# iot_ambilamp_rpi_shield.net
KiCad netlist of a schematic drawn in EAGLE
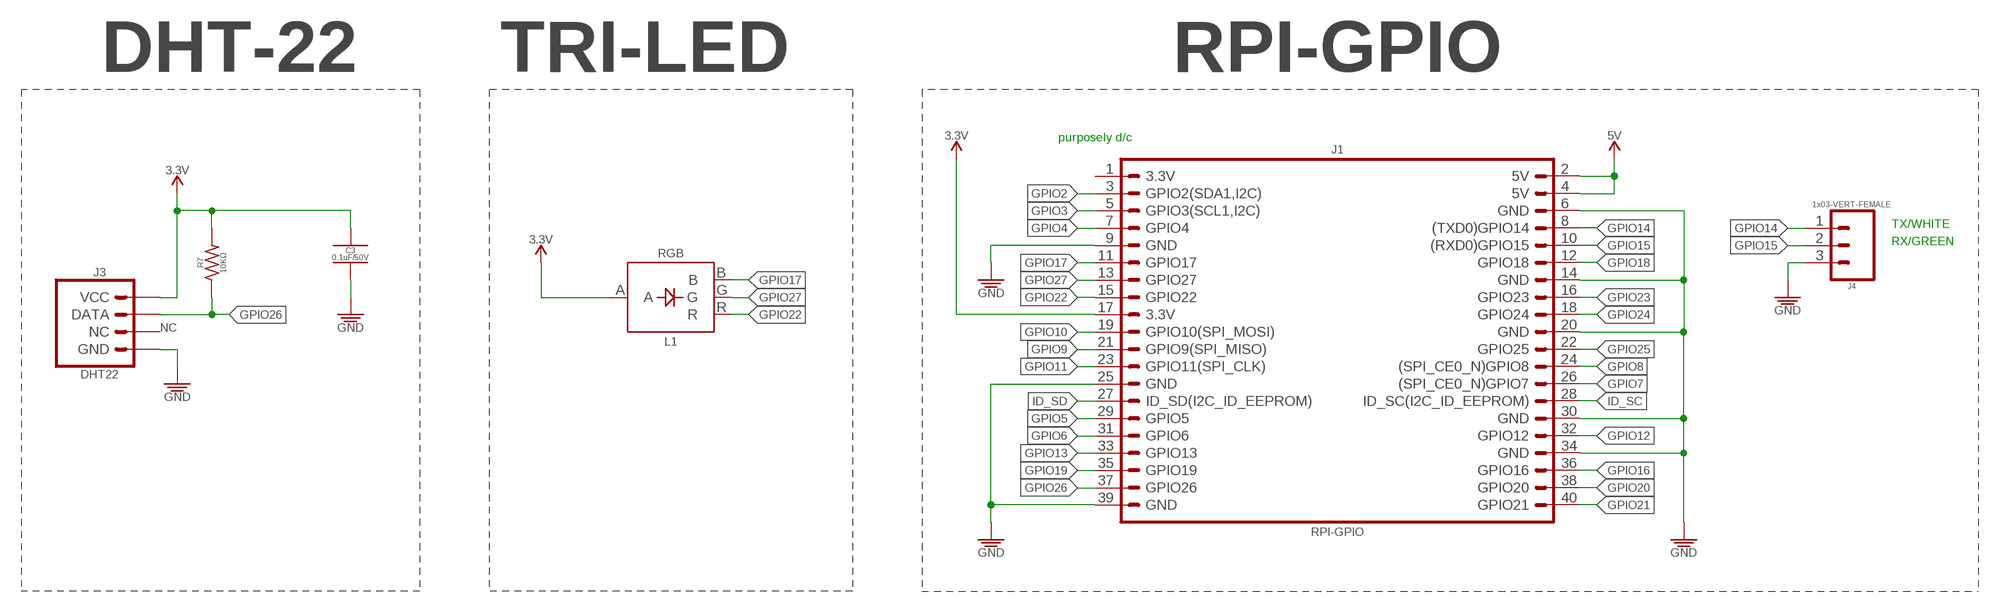
[diagram p0: schematic, sheet 1, part 1 of 2]
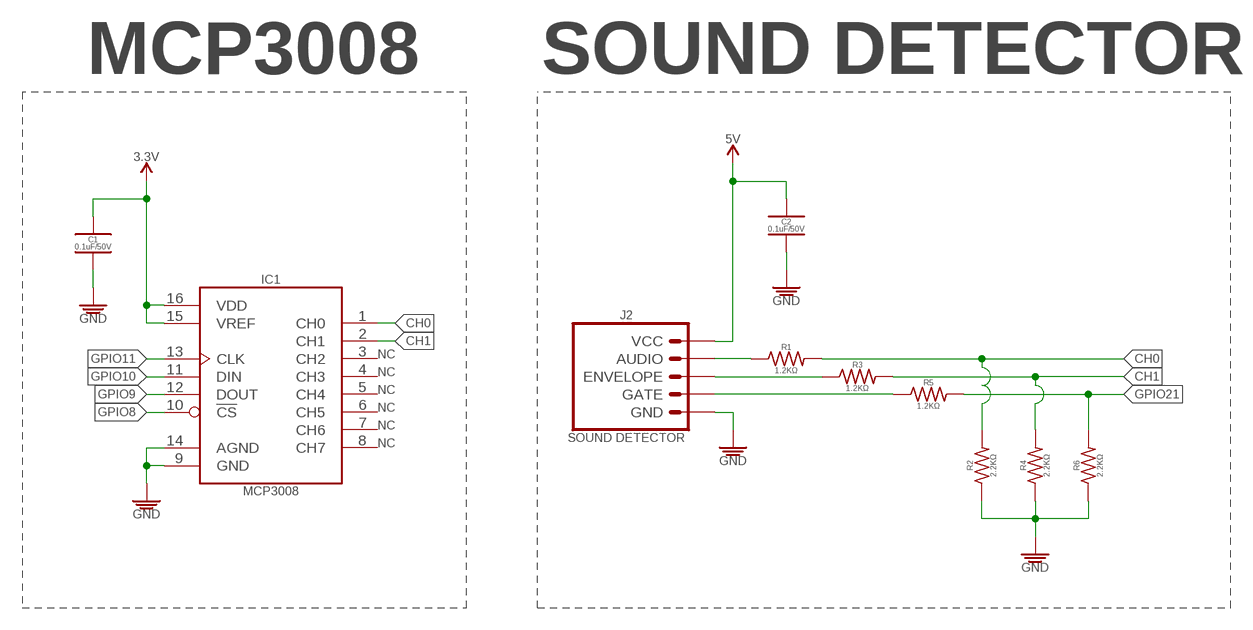
[diagram p1: schematic, sheet 1, part 2 of 2]

(export (version "E")
  (design (tool "Eeschema 10.0.6"))
  (components
    (comp (ref "C1")
      (value "0.1uF/50V")
      (footprint "eagle-import:_CER_SMD-805")
      (fields
        (field (name "MFR") "Murata Electronics North America")
        (field (name "MPN") "GRM21BR71H104KA01L")
        (field (name "CREATOR") "MrSwirlyEyes")
      )
      (libsource (lib "eagle-import") (part "0.1UF_SMD-805_50V-10%"))
    )
    (comp (ref "C2")
      (value "0.1uF/50V")
      (footprint "eagle-import:_CER_SMD-805")
      (fields
        (field (name "MFR") "Murata Electronics North America")
        (field (name "MPN") "GRM21BR71H104KA01L")
        (field (name "CREATOR") "MrSwirlyEyes")
      )
      (libsource (lib "eagle-import") (part "0.1UF_SMD-805_50V-10%"))
    )
    (comp (ref "C3")
      (value "0.1uF/50V")
      (footprint "eagle-import:_CER_SMD-805")
      (fields
        (field (name "MFR") "Murata Electronics North America")
        (field (name "MPN") "GRM21BR71H104KA01L")
        (field (name "CREATOR") "MrSwirlyEyes")
      )
      (libsource (lib "eagle-import") (part "0.1UF_SMD-805_50V-10%"))
    )
    (comp (ref "IC1")
      (value "MCP3008")
      (footprint "eagle-import:SO-16")
      (fields
        (field (name "MFR") "Microchip Technology")
        (field (name "MPN") "MCP3008-I/SL")
        (field (name "CREATOR") "MrSwirlyEyes")
      )
      (libsource (lib "eagle-import") (part "MCP3008SO-16"))
    )
    (comp (ref "J1")
      (value "RPI-GPIO")
      (footprint "eagle-import:RPI-GPIO_CONNECTOR_TALL")
      (fields
        (field (name "MFR") "Sparkfun Electronics")
        (field (name "MPN") "PRT-14017")
        (field (name "CREATOR") "MrSwirlyEyes")
      )
      (libsource (lib "eagle-import") (part "RPI-GPIO_CONNECTOR"))
    )
    (comp (ref "J2")
      (value "SOUND DETECTOR")
      (footprint "eagle-import:CONNECTOR-RA_SOUND-DETECTOR_SPARKFUN")
      (fields
        (field (name "MFR") "Sparkfun")
        (field (name "MPN") "SEN-12642")
        (field (name "CREATOR") "MrSwirlyEyes")
      )
      (libsource (lib "eagle-import") (part "SOUND-DETECTOR_SPARKFUN"))
    )
    (comp (ref "J3")
      (value "DHT22")
      (footprint "eagle-import:CONNECTOR_TEMPERATURE-SENSOR_DHT22")
      (fields
        (field (name "MFR") "MaxDetect Technology Co., Ltd.")
        (field (name "MPN") "RHT03")
        (field (name "CREATOR") "MrSwirlyEyes")
      )
      (libsource (lib "eagle-import") (part "TEMPERATURE-SENSOR_DHT22"))
    )
    (comp (ref "J4")
      (value "1x03-VERT-FEMALE")
      (footprint "eagle-import:1X03-VERT-FEMALE")
      (fields
        (field (name "MFR") "Sullins Connector Solutions")
        (field (name "MPN") "PPTC031LFBN-RC")
        (field (name "CREATOR") "MrSwirlyEyes")
      )
      (libsource (lib "eagle-import") (part "1X03_VERT-FEMALE"))
    )
    (comp (ref "L1")
      (value "RGB")
      (footprint "eagle-import:LED-5MM-PTH_RGB-CA")
      (fields
        (field (name "MFR") "SunLED")
        (field (name "MPN") "YSL-R596AR3G4B5C-C10")
        (field (name "CREATOR") "MrSwirlyEyes")
      )
      (libsource (lib "eagle-import") (part "LED-5MM-PTH_RGB-CA"))
    )
    (comp (ref "R1")
      (value "1.2KΩ")
      (footprint "eagle-import:RESISTOR_SMD-805")
      (fields
        (field (name "MFR") "Yageo")
        (field (name "MPN") "RC0805JR-071K2L")
        (field (name "CREATOR") "MrSwirlyEyes")
      )
      (libsource (lib "eagle-import") (part "1.2KΩ_SMD-0805_1/8W-5%"))
    )
    (comp (ref "R2")
      (value "2.2KΩ")
      (footprint "eagle-import:RESISTOR_SMD-805")
      (fields
        (field (name "MFR") "Yageo")
        (field (name "MPN") "RC0805JR-072K2L")
        (field (name "CREATOR") "MrSwirlyEyes")
      )
      (libsource (lib "eagle-import") (part "2.2KΩ_SMD-0805_1/8W-5%"))
    )
    (comp (ref "R3")
      (value "1.2KΩ")
      (footprint "eagle-import:RESISTOR_SMD-805")
      (fields
        (field (name "MFR") "Yageo")
        (field (name "MPN") "RC0805JR-071K2L")
        (field (name "CREATOR") "MrSwirlyEyes")
      )
      (libsource (lib "eagle-import") (part "1.2KΩ_SMD-0805_1/8W-5%"))
    )
    (comp (ref "R4")
      (value "2.2KΩ")
      (footprint "eagle-import:RESISTOR_SMD-805")
      (fields
        (field (name "MFR") "Yageo")
        (field (name "MPN") "RC0805JR-072K2L")
        (field (name "CREATOR") "MrSwirlyEyes")
      )
      (libsource (lib "eagle-import") (part "2.2KΩ_SMD-0805_1/8W-5%"))
    )
    (comp (ref "R5")
      (value "1.2KΩ")
      (footprint "eagle-import:RESISTOR_SMD-805")
      (fields
        (field (name "MFR") "Yageo")
        (field (name "MPN") "RC0805JR-071K2L")
        (field (name "CREATOR") "MrSwirlyEyes")
      )
      (libsource (lib "eagle-import") (part "1.2KΩ_SMD-0805_1/8W-5%"))
    )
    (comp (ref "R6")
      (value "2.2KΩ")
      (footprint "eagle-import:RESISTOR_SMD-805")
      (fields
        (field (name "MFR") "Yageo")
        (field (name "MPN") "RC0805JR-072K2L")
        (field (name "CREATOR") "MrSwirlyEyes")
      )
      (libsource (lib "eagle-import") (part "2.2KΩ_SMD-0805_1/8W-5%"))
    )
    (comp (ref "R7")
      (value "10KΩ")
      (footprint "eagle-import:RESISTOR_SMD-805")
      (fields
        (field (name "MFR") "Yageo")
        (field (name "MPN") "RC0805JR-0710KL")
        (field (name "CREATOR") "Kenmei")
      )
      (libsource (lib "eagle-import") (part "10KΩ_SMD-0805_1/8W-5%"))
    )
  )
  (nets
    (net (code "1") (name "3.3V") (class "Default")
      (node (ref "C1") (pin "1") (pinfunction "1_1") (pintype "passive"))
      (node (ref "C3") (pin "1") (pinfunction "1_1") (pintype "passive"))
      (node (ref "IC1") (pin "15") (pinfunction "VREF_15") (pintype "input"))
      (node (ref "IC1") (pin "16") (pinfunction "VDD_16") (pintype "power_in"))
      (node (ref "J1") (pin "17") (pinfunction "3.3V_17") (pintype "bidirectional"))
      (node (ref "J3") (pin "VCC") (pinfunction "VCC_VCC") (pintype "passive"))
      (node (ref "L1") (pin "A") (pinfunction "A_A") (pintype "bidirectional"))
      (node (ref "R7") (pin "2") (pinfunction "2_2") (pintype "passive"))
    )
    (net (code "2") (name "5V") (class "Default")
      (node (ref "C2") (pin "1") (pinfunction "1_1") (pintype "passive"))
      (node (ref "J1") (pin "2") (pinfunction "5V_2") (pintype "bidirectional"))
      (node (ref "J1") (pin "4") (pinfunction "5V_4") (pintype "bidirectional"))
      (node (ref "J2") (pin "VCC") (pinfunction "VCC_VCC") (pintype "passive"))
    )
    (net (code "3") (name "CH0") (class "Default")
      (node (ref "IC1") (pin "1") (pinfunction "CH0_1") (pintype "input"))
      (node (ref "R1") (pin "2") (pinfunction "2_2") (pintype "passive"))
      (node (ref "R2") (pin "2") (pinfunction "2_2") (pintype "passive"))
    )
    (net (code "4") (name "CH1") (class "Default")
      (node (ref "IC1") (pin "2") (pinfunction "CH1_2") (pintype "input"))
      (node (ref "R3") (pin "2") (pinfunction "2_2") (pintype "passive"))
      (node (ref "R4") (pin "2") (pinfunction "2_2") (pintype "passive"))
    )
    (net (code "5") (name "GND") (class "Default")
      (node (ref "C1") (pin "2") (pinfunction "2_2") (pintype "passive"))
      (node (ref "C2") (pin "2") (pinfunction "2_2") (pintype "passive"))
      (node (ref "C3") (pin "2") (pinfunction "2_2") (pintype "passive"))
      (node (ref "IC1") (pin "14") (pinfunction "AGND_14") (pintype "power_in"))
      (node (ref "IC1") (pin "9") (pinfunction "GND_9") (pintype "power_in"))
      (node (ref "J1") (pin "14") (pinfunction "GND_14") (pintype "bidirectional"))
      (node (ref "J1") (pin "20") (pinfunction "GND_20") (pintype "bidirectional"))
      (node (ref "J1") (pin "25") (pinfunction "GND_25") (pintype "bidirectional"))
      (node (ref "J1") (pin "30") (pinfunction "GND_30") (pintype "bidirectional"))
      (node (ref "J1") (pin "34") (pinfunction "GND_34") (pintype "bidirectional"))
      (node (ref "J1") (pin "39") (pinfunction "GND_39") (pintype "bidirectional"))
      (node (ref "J1") (pin "6") (pinfunction "GND_6") (pintype "bidirectional"))
      (node (ref "J1") (pin "9") (pinfunction "GND_9") (pintype "bidirectional"))
      (node (ref "J2") (pin "GND") (pinfunction "GND_GND") (pintype "passive"))
      (node (ref "J3") (pin "GND") (pinfunction "GND_GND") (pintype "passive"))
      (node (ref "J4") (pin "3") (pinfunction "3_3") (pintype "passive"))
      (node (ref "R2") (pin "1") (pinfunction "1_1") (pintype "passive"))
      (node (ref "R4") (pin "1") (pinfunction "1_1") (pintype "passive"))
      (node (ref "R6") (pin "1") (pinfunction "1_1") (pintype "passive"))
    )
    (net (code "6") (name "GPIO2") (class "Default")
      (node (ref "J1") (pin "3") (pinfunction "GPIO2(SDA1,I2C)_3") (pintype "bidirectional"))
    )
    (net (code "7") (name "GPIO3") (class "Default")
      (node (ref "J1") (pin "5") (pinfunction "GPIO3(SCL1,I2C)_5") (pintype "bidirectional"))
    )
    (net (code "8") (name "GPIO4") (class "Default")
      (node (ref "J1") (pin "7") (pinfunction "GPIO4_7") (pintype "bidirectional"))
    )
    (net (code "9") (name "GPIO5") (class "Default")
      (node (ref "J1") (pin "29") (pinfunction "GPIO5_29") (pintype "bidirectional"))
    )
    (net (code "10") (name "GPIO6") (class "Default")
      (node (ref "J1") (pin "31") (pinfunction "GPIO6_31") (pintype "bidirectional"))
    )
    (net (code "11") (name "GPIO7") (class "Default")
      (node (ref "J1") (pin "26") (pinfunction "(SPI_CE0_N)GPIO7_26") (pintype "bidirectional"))
    )
    (net (code "12") (name "GPIO8") (class "Default")
      (node (ref "IC1") (pin "10") (pinfunction "~{CS}_10") (pintype "input"))
      (node (ref "J1") (pin "24") (pinfunction "(SPI_CE0_N)GPIO8_24") (pintype "bidirectional"))
    )
    (net (code "13") (name "GPIO9") (class "Default")
      (node (ref "IC1") (pin "12") (pinfunction "DOUT_12") (pintype "output"))
      (node (ref "J1") (pin "21") (pinfunction "GPIO9(SPI_MISO)_21") (pintype "bidirectional"))
    )
    (net (code "14") (name "GPIO10") (class "Default")
      (node (ref "IC1") (pin "11") (pinfunction "DIN_11") (pintype "input"))
      (node (ref "J1") (pin "19") (pinfunction "GPIO10(SPI_MOSI)_19") (pintype "bidirectional"))
    )
    (net (code "15") (name "GPIO11") (class "Default")
      (node (ref "IC1") (pin "13") (pinfunction "CLK_13") (pintype "input"))
      (node (ref "J1") (pin "23") (pinfunction "GPIO11(SPI_CLK)_23") (pintype "bidirectional"))
    )
    (net (code "16") (name "GPIO12") (class "Default")
      (node (ref "J1") (pin "32") (pinfunction "GPIO12_32") (pintype "bidirectional"))
    )
    (net (code "17") (name "GPIO13") (class "Default")
      (node (ref "J1") (pin "33") (pinfunction "GPIO13_33") (pintype "bidirectional"))
    )
    (net (code "18") (name "GPIO14") (class "Default")
      (node (ref "J1") (pin "8") (pinfunction "(TXD0)GPIO14_8") (pintype "bidirectional"))
      (node (ref "J4") (pin "1") (pinfunction "1_1") (pintype "passive"))
    )
    (net (code "19") (name "GPIO15") (class "Default")
      (node (ref "J1") (pin "10") (pinfunction "(RXD0)GPIO15_10") (pintype "bidirectional"))
      (node (ref "J4") (pin "2") (pinfunction "2_2") (pintype "passive"))
    )
    (net (code "20") (name "GPIO16") (class "Default")
      (node (ref "J1") (pin "36") (pinfunction "GPIO16_36") (pintype "bidirectional"))
    )
    (net (code "21") (name "GPIO17") (class "Default")
      (node (ref "J1") (pin "11") (pinfunction "GPIO17_11") (pintype "bidirectional"))
      (node (ref "L1") (pin "B") (pinfunction "B_B") (pintype "bidirectional"))
    )
    (net (code "22") (name "GPIO18") (class "Default")
      (node (ref "J1") (pin "12") (pinfunction "GPIO18_12") (pintype "bidirectional"))
    )
    (net (code "23") (name "GPIO19") (class "Default")
      (node (ref "J1") (pin "35") (pinfunction "GPIO19_35") (pintype "bidirectional"))
    )
    (net (code "24") (name "GPIO20") (class "Default")
      (node (ref "J1") (pin "38") (pinfunction "GPIO20_38") (pintype "bidirectional"))
    )
    (net (code "25") (name "GPIO21") (class "Default")
      (node (ref "J1") (pin "40") (pinfunction "GPIO21_40") (pintype "bidirectional"))
      (node (ref "R5") (pin "2") (pinfunction "2_2") (pintype "passive"))
      (node (ref "R6") (pin "2") (pinfunction "2_2") (pintype "passive"))
    )
    (net (code "26") (name "GPIO22") (class "Default")
      (node (ref "J1") (pin "15") (pinfunction "GPIO22_15") (pintype "bidirectional"))
      (node (ref "L1") (pin "R") (pinfunction "R_R") (pintype "bidirectional"))
    )
    (net (code "27") (name "GPIO23") (class "Default")
      (node (ref "J1") (pin "16") (pinfunction "GPIO23_16") (pintype "bidirectional"))
    )
    (net (code "28") (name "GPIO24") (class "Default")
      (node (ref "J1") (pin "18") (pinfunction "GPIO24_18") (pintype "bidirectional"))
    )
    (net (code "29") (name "GPIO25") (class "Default")
      (node (ref "J1") (pin "22") (pinfunction "GPIO25_22") (pintype "bidirectional"))
    )
    (net (code "30") (name "GPIO26") (class "Default")
      (node (ref "J1") (pin "37") (pinfunction "GPIO26_37") (pintype "bidirectional"))
      (node (ref "J3") (pin "DATA") (pinfunction "DATA_DATA") (pintype "passive"))
      (node (ref "R7") (pin "1") (pinfunction "1_1") (pintype "passive"))
    )
    (net (code "31") (name "GPIO27") (class "Default")
      (node (ref "J1") (pin "13") (pinfunction "GPIO27_13") (pintype "bidirectional"))
      (node (ref "L1") (pin "G") (pinfunction "G_G") (pintype "bidirectional"))
    )
    (net (code "32") (name "ID_SC") (class "Default")
      (node (ref "J1") (pin "28") (pinfunction "ID_SC(I2C_ID_EEPROM)_28") (pintype "bidirectional"))
    )
    (net (code "33") (name "ID_SD") (class "Default")
      (node (ref "J1") (pin "27") (pinfunction "ID_SD(I2C_ID_EEPROM)_27") (pintype "bidirectional"))
    )
    (net (code "34") (name "Net-(J2-PadAUDIO)") (class "Default")
      (node (ref "J2") (pin "AUDIO") (pinfunction "AUDIO_AUDIO") (pintype "passive"))
      (node (ref "R1") (pin "1") (pinfunction "1_1") (pintype "passive"))
    )
    (net (code "35") (name "Net-(J2-PadENVELOPE)") (class "Default")
      (node (ref "J2") (pin "ENVELOPE") (pinfunction "ENVELOPE_ENVELOPE") (pintype "passive"))
      (node (ref "R3") (pin "1") (pinfunction "1_1") (pintype "passive"))
    )
    (net (code "36") (name "Net-(J2-PadGATE)") (class "Default")
      (node (ref "J2") (pin "GATE") (pinfunction "GATE_GATE") (pintype "passive"))
      (node (ref "R5") (pin "1") (pinfunction "1_1") (pintype "passive"))
    )
    (net (code "37") (name "unconnected-(IC1-CH2-Pad3)") (class "Default")
      (node (ref "IC1") (pin "3") (pinfunction "CH2_3") (pintype "input"))
    )
    (net (code "38") (name "unconnected-(IC1-CH3-Pad4)") (class "Default")
      (node (ref "IC1") (pin "4") (pinfunction "CH3_4") (pintype "input"))
    )
    (net (code "39") (name "unconnected-(IC1-CH4-Pad5)") (class "Default")
      (node (ref "IC1") (pin "5") (pinfunction "CH4_5") (pintype "input"))
    )
    (net (code "40") (name "unconnected-(IC1-CH5-Pad6)") (class "Default")
      (node (ref "IC1") (pin "6") (pinfunction "CH5_6") (pintype "input"))
    )
    (net (code "41") (name "unconnected-(IC1-CH6-Pad7)") (class "Default")
      (node (ref "IC1") (pin "7") (pinfunction "CH6_7") (pintype "input"))
    )
    (net (code "42") (name "unconnected-(IC1-CH7-Pad8)") (class "Default")
      (node (ref "IC1") (pin "8") (pinfunction "CH7_8") (pintype "input"))
    )
    (net (code "43") (name "unconnected-(J1-3.3V-Pad1)") (class "Default")
      (node (ref "J1") (pin "1") (pinfunction "3.3V_1") (pintype "bidirectional"))
    )
    (net (code "44") (name "unconnected-(J3-PadNC)") (class "Default")
      (node (ref "J3") (pin "NC") (pinfunction "NC_NC") (pintype "no_connect"))
    )
  )
)
